# Mussol.net
KiCad netlist of a schematic drawn in EAGLE
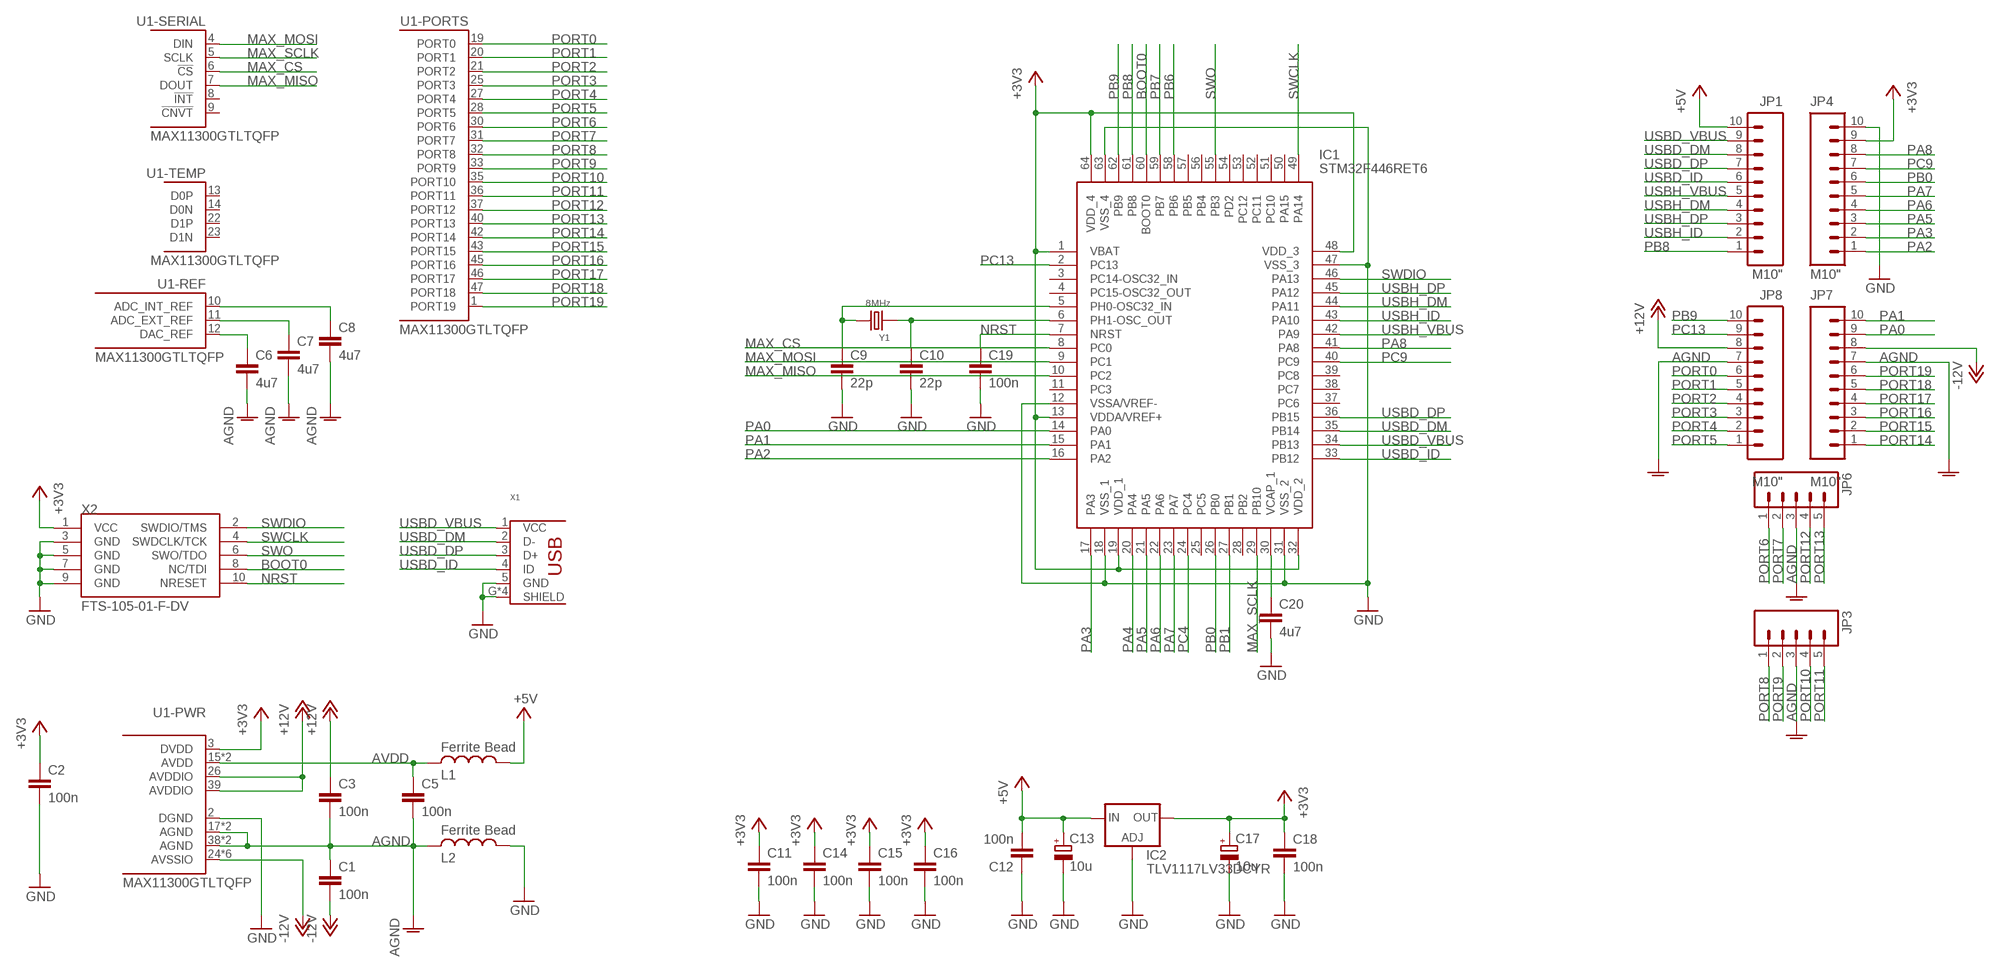
[diagram p0: schematic, sheet 1]

(export (version "E")
  (design (tool "Eeschema 10.0.6"))
  (components
    (comp (ref "C1")
      (value "100n")
      (footprint "eagle-import:C0402")
      (libsource (lib "eagle-import") (part "C-EUC0402"))
    )
    (comp (ref "C2")
      (value "100n")
      (footprint "eagle-import:C0402")
      (libsource (lib "eagle-import") (part "C-EUC0402"))
    )
    (comp (ref "C3")
      (value "100n")
      (footprint "eagle-import:C0402")
      (libsource (lib "eagle-import") (part "C-EUC0402"))
    )
    (comp (ref "C5")
      (value "100n")
      (footprint "eagle-import:C0402")
      (libsource (lib "eagle-import") (part "C-EUC0402"))
    )
    (comp (ref "C6")
      (value "4u7")
      (footprint "eagle-import:C0603")
      (libsource (lib "eagle-import") (part "C-EUC0603"))
    )
    (comp (ref "C7")
      (value "4u7")
      (footprint "eagle-import:C0603")
      (libsource (lib "eagle-import") (part "C-EUC0603"))
    )
    (comp (ref "C8")
      (value "4u7")
      (footprint "eagle-import:C0603")
      (libsource (lib "eagle-import") (part "C-EUC0603"))
    )
    (comp (ref "C9")
      (value "22p")
      (footprint "eagle-import:C0402")
      (libsource (lib "eagle-import") (part "C-EUC0402"))
    )
    (comp (ref "C10")
      (value "22p")
      (footprint "eagle-import:C0402")
      (libsource (lib "eagle-import") (part "C-EUC0402"))
    )
    (comp (ref "C11")
      (value "100n")
      (footprint "eagle-import:C0402")
      (libsource (lib "eagle-import") (part "C-EUC0402"))
    )
    (comp (ref "C12")
      (value "100n")
      (footprint "eagle-import:C0402")
      (libsource (lib "eagle-import") (part "C-EUC0402"))
    )
    (comp (ref "C13")
      (value "10u")
      (footprint "eagle-import:UD-4X5,8_NICHICON")
      (libsource (lib "eagle-import") (part "CPOL-EUUD-4X5,8"))
    )
    (comp (ref "C14")
      (value "100n")
      (footprint "eagle-import:C0402")
      (libsource (lib "eagle-import") (part "C-EUC0402"))
    )
    (comp (ref "C15")
      (value "100n")
      (footprint "eagle-import:C0402")
      (libsource (lib "eagle-import") (part "C-EUC0402"))
    )
    (comp (ref "C16")
      (value "100n")
      (footprint "eagle-import:C0402")
      (libsource (lib "eagle-import") (part "C-EUC0402"))
    )
    (comp (ref "C17")
      (value "10u")
      (footprint "eagle-import:UD-4X5,8_NICHICON")
      (libsource (lib "eagle-import") (part "CPOL-EUUD-4X5,8"))
    )
    (comp (ref "C18")
      (value "100n")
      (footprint "eagle-import:C0402")
      (libsource (lib "eagle-import") (part "C-EUC0402"))
    )
    (comp (ref "C19")
      (value "100n")
      (footprint "eagle-import:C0402")
      (libsource (lib "eagle-import") (part "C-EUC0402"))
    )
    (comp (ref "C20")
      (value "4u7")
      (footprint "eagle-import:C0603")
      (libsource (lib "eagle-import") (part "C-EUC0603"))
    )
    (comp (ref "IC1")
      (value "STM32F446RET6")
      (footprint "eagle-import:QFP50P1200X1200X160-64N")
      (fields
        (field (name "MOUSER_PART_NUMBER") "511-STM32F446RET6")
        (field (name "RS_PART_NUMBER") "1106621P")
      )
      (libsource (lib "eagle-import") (part "STM32F446RET6"))
    )
    (comp (ref "IC2")
      (value "TLV1117LV33DCYR")
      (footprint "eagle-import:SOT223")
      (libsource (lib "eagle-import") (part "LD117A?S33TR"))
    )
    (comp (ref "JP1")
      (value "M10\"")
      (footprint "eagle-import:1X10")
      (libsource (lib "eagle-import") (part "M10{dblquote}"))
    )
    (comp (ref "JP3")
      (value "M05PTH")
      (footprint "eagle-import:1X05")
      (libsource (lib "eagle-import") (part "M05PTH"))
    )
    (comp (ref "JP4")
      (value "M10\"")
      (footprint "eagle-import:1X10")
      (libsource (lib "eagle-import") (part "M10{dblquote}"))
    )
    (comp (ref "JP6")
      (value "M05PTH")
      (footprint "eagle-import:1X05")
      (libsource (lib "eagle-import") (part "M05PTH"))
    )
    (comp (ref "JP7")
      (value "M10\"")
      (footprint "eagle-import:1X10")
      (libsource (lib "eagle-import") (part "M10{dblquote}"))
    )
    (comp (ref "JP8")
      (value "M10\"")
      (footprint "eagle-import:1X10")
      (libsource (lib "eagle-import") (part "M10{dblquote}"))
    )
    (comp (ref "L1")
      (value "Ferrite Bead")
      (footprint "eagle-import:0603")
      (libsource (lib "eagle-import") (part "INDUCTOR"))
    )
    (comp (ref "L2")
      (value "Ferrite Bead")
      (footprint "eagle-import:0603")
      (libsource (lib "eagle-import") (part "INDUCTOR"))
    )
    (comp (ref "U1")
      (value "MAX11300GTLTQFP")
      (footprint "eagle-import:TQFP48")
      (libsource (lib "eagle-import") (part "MAX11300GTLTQFP"))
    )
    (comp (ref "X1")
      (value "USB_HRS_ZX62-B-5PA(11)MICRO.B")
      (footprint "eagle-import:HRS_ZX62RD-AB-5P8")
      (libsource (lib "eagle-import") (part "USB_HRS_ZX62-B-5PA(11)MICRO.B"))
    )
    (comp (ref "X2")
      (value "FTS-105-01-F-DV")
      (footprint "eagle-import:2X5_1.27MM_SMD")
      (libsource (lib "eagle-import") (part "ARM_10SMD"))
    )
    (comp (ref "Y1")
      (value "8MHz")
      (footprint "eagle-import:X2-SMD-5.0X3.2X1.3MM")
      (fields (field (name "MPN") "5032/2P"))
      (libsource (lib "eagle-import") (part "SMD-CRYSTAL-8MHZ-20PF-20PPM(2P-5.0X3.2MM)"))
    )
  )
  (nets
    (net (code "1") (name "+3V3") (class "Default")
      (node (ref "C11") (pin "1") (pinfunction "1_1") (pintype "passive"))
      (node (ref "C14") (pin "1") (pinfunction "1_1") (pintype "passive"))
      (node (ref "C15") (pin "1") (pinfunction "1_1") (pintype "passive"))
      (node (ref "C16") (pin "1") (pinfunction "1_1") (pintype "passive"))
      (node (ref "C17") (pin "+") (pinfunction "+_+") (pintype "passive"))
      (node (ref "C18") (pin "1") (pinfunction "1_1") (pintype "passive"))
      (node (ref "C2") (pin "1") (pinfunction "1_1") (pintype "passive"))
      (node (ref "IC1") (pin "1") (pinfunction "VBAT_1") (pintype "bidirectional"))
      (node (ref "IC1") (pin "13") (pinfunction "VDDA/VREF+_13") (pintype "bidirectional"))
      (node (ref "IC1") (pin "19") (pinfunction "VDD_1_19") (pintype "bidirectional"))
      (node (ref "IC1") (pin "32") (pinfunction "VDD_2_32") (pintype "bidirectional"))
      (node (ref "IC1") (pin "48") (pinfunction "VDD_3_48") (pintype "bidirectional"))
      (node (ref "IC1") (pin "64") (pinfunction "VDD_4_64") (pintype "bidirectional"))
      (node (ref "IC2") (pin "4") (pinfunction "OUT_4") (pintype "passive"))
      (node (ref "JP4") (pin "9") (pinfunction "9_9") (pintype "passive"))
      (node (ref "U1") (pin "3") (pinfunction "DVDD_3") (pintype "bidirectional"))
      (node (ref "X2") (pin "1") (pinfunction "VCC_1") (pintype "bidirectional"))
    )
    (net (code "2") (name "+5V") (class "Default")
      (node (ref "C12") (pin "2") (pinfunction "2_2") (pintype "passive"))
      (node (ref "C13") (pin "+") (pinfunction "+_+") (pintype "passive"))
      (node (ref "IC2") (pin "3") (pinfunction "IN_3") (pintype "input"))
      (node (ref "JP1") (pin "10") (pinfunction "10_10") (pintype "passive"))
      (node (ref "L1") (pin "1") (pinfunction "1_1") (pintype "passive"))
    )
    (net (code "3") (name "+12V") (class "Default")
      (node (ref "C3") (pin "1") (pinfunction "1_1") (pintype "passive"))
      (node (ref "JP8") (pin "8") (pinfunction "8_8") (pintype "passive"))
      (node (ref "U1") (pin "26") (pinfunction "AVDDIO_26") (pintype "bidirectional"))
      (node (ref "U1") (pin "39") (pinfunction "AVDDIO_39") (pintype "bidirectional"))
    )
    (net (code "4") (name "-12V") (class "Default")
      (node (ref "C1") (pin "2") (pinfunction "2_2") (pintype "passive"))
      (node (ref "JP7") (pin "8") (pinfunction "8_8") (pintype "passive"))
      (node (ref "U1") (pin "24") (pinfunction "AVSSIO_24") (pintype "bidirectional"))
      (node (ref "U1") (pin "29") (pinfunction "AVSSIO_29") (pintype "bidirectional"))
      (node (ref "U1") (pin "34") (pinfunction "AVSSIO_34") (pintype "bidirectional"))
      (node (ref "U1") (pin "41") (pinfunction "AVSSIO_41") (pintype "bidirectional"))
      (node (ref "U1") (pin "44") (pinfunction "AVSSIO_44") (pintype "bidirectional"))
      (node (ref "U1") (pin "48") (pinfunction "AVSSIO_48") (pintype "bidirectional"))
    )
    (net (code "5") (name "/AVDD") (class "Default")
      (node (ref "C5") (pin "1") (pinfunction "1_1") (pintype "passive"))
      (node (ref "L1") (pin "2") (pinfunction "2_2") (pintype "passive"))
      (node (ref "U1") (pin "15") (pinfunction "AVDD_15") (pintype "bidirectional"))
      (node (ref "U1") (pin "16") (pinfunction "AVDD_16") (pintype "bidirectional"))
    )
    (net (code "6") (name "/BOOT0") (class "Default")
      (node (ref "IC1") (pin "60") (pinfunction "BOOT0_60") (pintype "bidirectional"))
      (node (ref "X2") (pin "8") (pinfunction "NC/TDI_8") (pintype "bidirectional"))
    )
    (net (code "7") (name "/MAX_CS") (class "Default")
      (node (ref "IC1") (pin "8") (pinfunction "PC0_8") (pintype "bidirectional"))
      (node (ref "U1") (pin "6") (pinfunction "~{CS}_6") (pintype "bidirectional"))
    )
    (net (code "8") (name "/MAX_MISO") (class "Default")
      (node (ref "IC1") (pin "10") (pinfunction "PC2_10") (pintype "bidirectional"))
      (node (ref "U1") (pin "7") (pinfunction "DOUT_7") (pintype "bidirectional"))
    )
    (net (code "9") (name "/MAX_MOSI") (class "Default")
      (node (ref "IC1") (pin "9") (pinfunction "PC1_9") (pintype "bidirectional"))
      (node (ref "U1") (pin "4") (pinfunction "DIN_4") (pintype "bidirectional"))
    )
    (net (code "10") (name "/MAX_SCLK") (class "Default")
      (node (ref "IC1") (pin "29") (pinfunction "PB10_29") (pintype "bidirectional"))
      (node (ref "U1") (pin "5") (pinfunction "SCLK_5") (pintype "bidirectional"))
    )
    (net (code "11") (name "/NRST") (class "Default")
      (node (ref "C19") (pin "1") (pinfunction "1_1") (pintype "passive"))
      (node (ref "IC1") (pin "7") (pinfunction "NRST_7") (pintype "bidirectional"))
      (node (ref "X2") (pin "10") (pinfunction "NRESET_10") (pintype "bidirectional"))
    )
    (net (code "12") (name "/PA0") (class "Default")
      (node (ref "IC1") (pin "14") (pinfunction "PA0_14") (pintype "bidirectional"))
      (node (ref "JP7") (pin "9") (pinfunction "9_9") (pintype "passive"))
    )
    (net (code "13") (name "/PA1") (class "Default")
      (node (ref "IC1") (pin "15") (pinfunction "PA1_15") (pintype "bidirectional"))
      (node (ref "JP7") (pin "10") (pinfunction "10_10") (pintype "passive"))
    )
    (net (code "14") (name "/PA2") (class "Default")
      (node (ref "IC1") (pin "16") (pinfunction "PA2_16") (pintype "bidirectional"))
      (node (ref "JP4") (pin "1") (pinfunction "1_1") (pintype "passive"))
    )
    (net (code "15") (name "/PA3") (class "Default")
      (node (ref "IC1") (pin "17") (pinfunction "PA3_17") (pintype "bidirectional"))
      (node (ref "JP4") (pin "2") (pinfunction "2_2") (pintype "passive"))
    )
    (net (code "16") (name "/PA4") (class "Default")
      (node (ref "IC1") (pin "20") (pinfunction "PA4_20") (pintype "bidirectional"))
    )
    (net (code "17") (name "/PA5") (class "Default")
      (node (ref "IC1") (pin "21") (pinfunction "PA5_21") (pintype "bidirectional"))
      (node (ref "JP4") (pin "3") (pinfunction "3_3") (pintype "passive"))
    )
    (net (code "18") (name "/PA6") (class "Default")
      (node (ref "IC1") (pin "22") (pinfunction "PA6_22") (pintype "bidirectional"))
      (node (ref "JP4") (pin "4") (pinfunction "4_4") (pintype "passive"))
    )
    (net (code "19") (name "/PA7") (class "Default")
      (node (ref "IC1") (pin "23") (pinfunction "PA7_23") (pintype "bidirectional"))
      (node (ref "JP4") (pin "5") (pinfunction "5_5") (pintype "passive"))
    )
    (net (code "20") (name "/PA8") (class "Default")
      (node (ref "IC1") (pin "41") (pinfunction "PA8_41") (pintype "bidirectional"))
      (node (ref "JP4") (pin "8") (pinfunction "8_8") (pintype "passive"))
    )
    (net (code "21") (name "/PB0") (class "Default")
      (node (ref "IC1") (pin "26") (pinfunction "PB0_26") (pintype "bidirectional"))
      (node (ref "JP4") (pin "6") (pinfunction "6_6") (pintype "passive"))
    )
    (net (code "22") (name "/PB1") (class "Default")
      (node (ref "IC1") (pin "27") (pinfunction "PB1_27") (pintype "bidirectional"))
    )
    (net (code "23") (name "/PB6") (class "Default")
      (node (ref "IC1") (pin "58") (pinfunction "PB6_58") (pintype "bidirectional"))
    )
    (net (code "24") (name "/PB7") (class "Default")
      (node (ref "IC1") (pin "59") (pinfunction "PB7_59") (pintype "bidirectional"))
    )
    (net (code "25") (name "/PB8") (class "Default")
      (node (ref "IC1") (pin "61") (pinfunction "PB8_61") (pintype "bidirectional"))
      (node (ref "JP1") (pin "1") (pinfunction "1_1") (pintype "passive"))
    )
    (net (code "26") (name "/PB9") (class "Default")
      (node (ref "IC1") (pin "62") (pinfunction "PB9_62") (pintype "bidirectional"))
      (node (ref "JP8") (pin "10") (pinfunction "10_10") (pintype "passive"))
    )
    (net (code "27") (name "/PC4") (class "Default")
      (node (ref "IC1") (pin "24") (pinfunction "PC4_24") (pintype "bidirectional"))
    )
    (net (code "28") (name "/PC9") (class "Default")
      (node (ref "IC1") (pin "40") (pinfunction "PC9_40") (pintype "bidirectional"))
      (node (ref "JP4") (pin "7") (pinfunction "7_7") (pintype "passive"))
    )
    (net (code "29") (name "/PC13") (class "Default")
      (node (ref "IC1") (pin "2") (pinfunction "PC13_2") (pintype "bidirectional"))
      (node (ref "JP8") (pin "9") (pinfunction "9_9") (pintype "passive"))
    )
    (net (code "30") (name "/PORT0") (class "Default")
      (node (ref "JP8") (pin "6") (pinfunction "6_6") (pintype "passive"))
      (node (ref "U1") (pin "19") (pinfunction "PORT0_19") (pintype "bidirectional"))
    )
    (net (code "31") (name "/PORT1") (class "Default")
      (node (ref "JP8") (pin "5") (pinfunction "5_5") (pintype "passive"))
      (node (ref "U1") (pin "20") (pinfunction "PORT1_20") (pintype "bidirectional"))
    )
    (net (code "32") (name "/PORT2") (class "Default")
      (node (ref "JP8") (pin "4") (pinfunction "4_4") (pintype "passive"))
      (node (ref "U1") (pin "21") (pinfunction "PORT2_21") (pintype "bidirectional"))
    )
    (net (code "33") (name "/PORT3") (class "Default")
      (node (ref "JP8") (pin "3") (pinfunction "3_3") (pintype "passive"))
      (node (ref "U1") (pin "25") (pinfunction "PORT3_25") (pintype "bidirectional"))
    )
    (net (code "34") (name "/PORT4") (class "Default")
      (node (ref "JP8") (pin "2") (pinfunction "2_2") (pintype "passive"))
      (node (ref "U1") (pin "27") (pinfunction "PORT4_27") (pintype "bidirectional"))
    )
    (net (code "35") (name "/PORT5") (class "Default")
      (node (ref "JP8") (pin "1") (pinfunction "1_1") (pintype "passive"))
      (node (ref "U1") (pin "28") (pinfunction "PORT5_28") (pintype "bidirectional"))
    )
    (net (code "36") (name "/PORT6") (class "Default")
      (node (ref "JP6") (pin "1") (pinfunction "1_1") (pintype "passive"))
      (node (ref "U1") (pin "30") (pinfunction "PORT6_30") (pintype "bidirectional"))
    )
    (net (code "37") (name "/PORT7") (class "Default")
      (node (ref "JP6") (pin "2") (pinfunction "2_2") (pintype "passive"))
      (node (ref "U1") (pin "31") (pinfunction "PORT7_31") (pintype "bidirectional"))
    )
    (net (code "38") (name "/PORT8") (class "Default")
      (node (ref "JP3") (pin "1") (pinfunction "1_1") (pintype "passive"))
      (node (ref "U1") (pin "32") (pinfunction "PORT8_32") (pintype "bidirectional"))
    )
    (net (code "39") (name "/PORT9") (class "Default")
      (node (ref "JP3") (pin "2") (pinfunction "2_2") (pintype "passive"))
      (node (ref "U1") (pin "33") (pinfunction "PORT9_33") (pintype "bidirectional"))
    )
    (net (code "40") (name "/PORT10") (class "Default")
      (node (ref "JP3") (pin "4") (pinfunction "4_4") (pintype "passive"))
      (node (ref "U1") (pin "35") (pinfunction "PORT10_35") (pintype "bidirectional"))
    )
    (net (code "41") (name "/PORT11") (class "Default")
      (node (ref "JP3") (pin "5") (pinfunction "5_5") (pintype "passive"))
      (node (ref "U1") (pin "36") (pinfunction "PORT11_36") (pintype "bidirectional"))
    )
    (net (code "42") (name "/PORT12") (class "Default")
      (node (ref "JP6") (pin "4") (pinfunction "4_4") (pintype "passive"))
      (node (ref "U1") (pin "37") (pinfunction "PORT12_37") (pintype "bidirectional"))
    )
    (net (code "43") (name "/PORT13") (class "Default")
      (node (ref "JP6") (pin "5") (pinfunction "5_5") (pintype "passive"))
      (node (ref "U1") (pin "40") (pinfunction "PORT13_40") (pintype "bidirectional"))
    )
    (net (code "44") (name "/PORT14") (class "Default")
      (node (ref "JP7") (pin "1") (pinfunction "1_1") (pintype "passive"))
      (node (ref "U1") (pin "42") (pinfunction "PORT14_42") (pintype "bidirectional"))
    )
    (net (code "45") (name "/PORT15") (class "Default")
      (node (ref "JP7") (pin "2") (pinfunction "2_2") (pintype "passive"))
      (node (ref "U1") (pin "43") (pinfunction "PORT15_43") (pintype "bidirectional"))
    )
    (net (code "46") (name "/PORT16") (class "Default")
      (node (ref "JP7") (pin "3") (pinfunction "3_3") (pintype "passive"))
      (node (ref "U1") (pin "45") (pinfunction "PORT16_45") (pintype "bidirectional"))
    )
    (net (code "47") (name "/PORT17") (class "Default")
      (node (ref "JP7") (pin "4") (pinfunction "4_4") (pintype "passive"))
      (node (ref "U1") (pin "46") (pinfunction "PORT17_46") (pintype "bidirectional"))
    )
    (net (code "48") (name "/PORT18") (class "Default")
      (node (ref "JP7") (pin "5") (pinfunction "5_5") (pintype "passive"))
      (node (ref "U1") (pin "47") (pinfunction "PORT18_47") (pintype "bidirectional"))
    )
    (net (code "49") (name "/PORT19") (class "Default")
      (node (ref "JP7") (pin "6") (pinfunction "6_6") (pintype "passive"))
      (node (ref "U1") (pin "1") (pinfunction "PORT19_1") (pintype "bidirectional"))
    )
    (net (code "50") (name "/SWCLK") (class "Default")
      (node (ref "IC1") (pin "49") (pinfunction "PA14_49") (pintype "bidirectional"))
      (node (ref "X2") (pin "4") (pinfunction "SWDCLK/TCK_4") (pintype "bidirectional"))
    )
    (net (code "51") (name "/SWDIO") (class "Default")
      (node (ref "IC1") (pin "46") (pinfunction "PA13_46") (pintype "bidirectional"))
      (node (ref "X2") (pin "2") (pinfunction "SWDIO/TMS_2") (pintype "bidirectional"))
    )
    (net (code "52") (name "/SWO") (class "Default")
      (node (ref "IC1") (pin "55") (pinfunction "PB3_55") (pintype "bidirectional"))
      (node (ref "X2") (pin "6") (pinfunction "SWO/TDO_6") (pintype "bidirectional"))
    )
    (net (code "53") (name "/USBD_DM") (class "Default")
      (node (ref "IC1") (pin "35") (pinfunction "PB14_35") (pintype "bidirectional"))
      (node (ref "JP1") (pin "8") (pinfunction "8_8") (pintype "passive"))
      (node (ref "X1") (pin "2") (pinfunction "D-_2") (pintype "bidirectional"))
    )
    (net (code "54") (name "/USBD_DP") (class "Default")
      (node (ref "IC1") (pin "36") (pinfunction "PB15_36") (pintype "bidirectional"))
      (node (ref "JP1") (pin "7") (pinfunction "7_7") (pintype "passive"))
      (node (ref "X1") (pin "3") (pinfunction "D+_3") (pintype "bidirectional"))
    )
    (net (code "55") (name "/USBD_ID") (class "Default")
      (node (ref "IC1") (pin "33") (pinfunction "PB12_33") (pintype "bidirectional"))
      (node (ref "JP1") (pin "6") (pinfunction "6_6") (pintype "passive"))
      (node (ref "X1") (pin "4") (pinfunction "ID_4") (pintype "bidirectional"))
    )
    (net (code "56") (name "/USBD_VBUS") (class "Default")
      (node (ref "IC1") (pin "34") (pinfunction "PB13_34") (pintype "bidirectional"))
      (node (ref "JP1") (pin "9") (pinfunction "9_9") (pintype "passive"))
      (node (ref "X1") (pin "1") (pinfunction "VCC_1") (pintype "bidirectional"))
    )
    (net (code "57") (name "/USBH_DM") (class "Default")
      (node (ref "IC1") (pin "44") (pinfunction "PA11_44") (pintype "bidirectional"))
      (node (ref "JP1") (pin "4") (pinfunction "4_4") (pintype "passive"))
    )
    (net (code "58") (name "/USBH_DP") (class "Default")
      (node (ref "IC1") (pin "45") (pinfunction "PA12_45") (pintype "bidirectional"))
      (node (ref "JP1") (pin "3") (pinfunction "3_3") (pintype "passive"))
    )
    (net (code "59") (name "/USBH_ID") (class "Default")
      (node (ref "IC1") (pin "43") (pinfunction "PA10_43") (pintype "bidirectional"))
      (node (ref "JP1") (pin "2") (pinfunction "2_2") (pintype "passive"))
    )
    (net (code "60") (name "/USBH_VBUS") (class "Default")
      (node (ref "IC1") (pin "42") (pinfunction "PA9_42") (pintype "bidirectional"))
      (node (ref "JP1") (pin "5") (pinfunction "5_5") (pintype "passive"))
    )
    (net (code "61") (name "AGND") (class "Default")
      (node (ref "C1") (pin "1") (pinfunction "1_1") (pintype "passive"))
      (node (ref "C3") (pin "2") (pinfunction "2_2") (pintype "passive"))
      (node (ref "C5") (pin "2") (pinfunction "2_2") (pintype "passive"))
      (node (ref "C6") (pin "2") (pinfunction "2_2") (pintype "passive"))
      (node (ref "C7") (pin "2") (pinfunction "2_2") (pintype "passive"))
      (node (ref "C8") (pin "2") (pinfunction "2_2") (pintype "passive"))
      (node (ref "JP3") (pin "3") (pinfunction "3_3") (pintype "passive"))
      (node (ref "JP6") (pin "3") (pinfunction "3_3") (pintype "passive"))
      (node (ref "JP7") (pin "7") (pinfunction "7_7") (pintype "passive"))
      (node (ref "JP8") (pin "7") (pinfunction "7_7") (pintype "passive"))
      (node (ref "L2") (pin "2") (pinfunction "2_2") (pintype "passive"))
      (node (ref "U1") (pin "17") (pinfunction "AGND_17") (pintype "bidirectional"))
      (node (ref "U1") (pin "18") (pinfunction "AGND_18") (pintype "bidirectional"))
      (node (ref "U1") (pin "38") (pinfunction "AGND_38") (pintype "bidirectional"))
      (node (ref "U1") (pin "EP") (pinfunction "AGND_EP") (pintype "bidirectional"))
    )
    (net (code "62") (name "GND") (class "Default")
      (node (ref "C10") (pin "2") (pinfunction "2_2") (pintype "passive"))
      (node (ref "C11") (pin "2") (pinfunction "2_2") (pintype "passive"))
      (node (ref "C12") (pin "1") (pinfunction "1_1") (pintype "passive"))
      (node (ref "C13") (pin "-") (pinfunction "-_-") (pintype "passive"))
      (node (ref "C14") (pin "2") (pinfunction "2_2") (pintype "passive"))
      (node (ref "C15") (pin "2") (pinfunction "2_2") (pintype "passive"))
      (node (ref "C16") (pin "2") (pinfunction "2_2") (pintype "passive"))
      (node (ref "C17") (pin "-") (pinfunction "-_-") (pintype "passive"))
      (node (ref "C18") (pin "2") (pinfunction "2_2") (pintype "passive"))
      (node (ref "C19") (pin "2") (pinfunction "2_2") (pintype "passive"))
      (node (ref "C2") (pin "2") (pinfunction "2_2") (pintype "passive"))
      (node (ref "C20") (pin "2") (pinfunction "2_2") (pintype "passive"))
      (node (ref "C9") (pin "2") (pinfunction "2_2") (pintype "passive"))
      (node (ref "IC1") (pin "12") (pinfunction "VSSA/VREF-_12") (pintype "bidirectional"))
      (node (ref "IC1") (pin "18") (pinfunction "VSS_1_18") (pintype "bidirectional"))
      (node (ref "IC1") (pin "31") (pinfunction "VSS_2_31") (pintype "bidirectional"))
      (node (ref "IC1") (pin "47") (pinfunction "VSS_3_47") (pintype "bidirectional"))
      (node (ref "IC1") (pin "63") (pinfunction "VSS_4_63") (pintype "bidirectional"))
      (node (ref "IC2") (pin "1") (pinfunction "ADJ_1") (pintype "input"))
      (node (ref "JP4") (pin "10") (pinfunction "10_10") (pintype "passive"))
      (node (ref "L2") (pin "1") (pinfunction "1_1") (pintype "passive"))
      (node (ref "U1") (pin "2") (pinfunction "DGND_2") (pintype "bidirectional"))
      (node (ref "X1") (pin "5") (pinfunction "GND_5") (pintype "bidirectional"))
      (node (ref "X1") (pin "G") (pinfunction "SHIELD_G") (pintype "bidirectional"))
      (node (ref "X1") (pin "G2") (pinfunction "SHIELD_G2") (pintype "bidirectional"))
      (node (ref "X1") (pin "G3") (pinfunction "SHIELD_G3") (pintype "bidirectional"))
      (node (ref "X1") (pin "G4") (pinfunction "SHIELD_G4") (pintype "bidirectional"))
      (node (ref "X2") (pin "3") (pinfunction "GND_3") (pintype "bidirectional"))
      (node (ref "X2") (pin "5") (pinfunction "GND_5") (pintype "bidirectional"))
      (node (ref "X2") (pin "7") (pinfunction "GND_7") (pintype "bidirectional"))
      (node (ref "X2") (pin "9") (pinfunction "GND_9") (pintype "bidirectional"))
    )
    (net (code "63") (name "Net-(IC1-PH0-OSC32_IN)") (class "Default")
      (node (ref "C9") (pin "1") (pinfunction "1_1") (pintype "passive"))
      (node (ref "IC1") (pin "5") (pinfunction "PH0-OSC32_IN_5") (pintype "bidirectional"))
      (node (ref "Y1") (pin "2") (pinfunction "2_2") (pintype "passive"))
    )
    (net (code "64") (name "Net-(IC1-PH1-OSC_OUT)") (class "Default")
      (node (ref "C10") (pin "1") (pinfunction "1_1") (pintype "passive"))
      (node (ref "IC1") (pin "6") (pinfunction "PH1-OSC_OUT_6") (pintype "bidirectional"))
      (node (ref "Y1") (pin "1") (pinfunction "1_1") (pintype "passive"))
    )
    (net (code "65") (name "Net-(IC1-VCAP_1)") (class "Default")
      (node (ref "C20") (pin "1") (pinfunction "1_1") (pintype "passive"))
      (node (ref "IC1") (pin "30") (pinfunction "VCAP_1_30") (pintype "bidirectional"))
    )
    (net (code "66") (name "Net-(U1C-ADC_EXT_REF)") (class "Default")
      (node (ref "C7") (pin "1") (pinfunction "1_1") (pintype "passive"))
      (node (ref "U1") (pin "11") (pinfunction "ADC_EXT_REF_11") (pintype "bidirectional"))
    )
    (net (code "67") (name "Net-(U1C-ADC_INT_REF)") (class "Default")
      (node (ref "C8") (pin "1") (pinfunction "1_1") (pintype "passive"))
      (node (ref "U1") (pin "10") (pinfunction "ADC_INT_REF_10") (pintype "bidirectional"))
    )
    (net (code "68") (name "Net-(U1C-DAC_REF)") (class "Default")
      (node (ref "C6") (pin "1") (pinfunction "1_1") (pintype "passive"))
      (node (ref "U1") (pin "12") (pinfunction "DAC_REF_12") (pintype "bidirectional"))
    )
    (net (code "69") (name "unconnected-(IC1-PA15-Pad50)") (class "Default")
      (node (ref "IC1") (pin "50") (pinfunction "PA15_50") (pintype "bidirectional"))
    )
    (net (code "70") (name "unconnected-(IC1-PB2-Pad28)") (class "Default")
      (node (ref "IC1") (pin "28") (pinfunction "PB2_28") (pintype "bidirectional"))
    )
    (net (code "71") (name "unconnected-(IC1-PB4-Pad56)") (class "Default")
      (node (ref "IC1") (pin "56") (pinfunction "PB4_56") (pintype "bidirectional"))
    )
    (net (code "72") (name "unconnected-(IC1-PB5-Pad57)") (class "Default")
      (node (ref "IC1") (pin "57") (pinfunction "PB5_57") (pintype "bidirectional"))
    )
    (net (code "73") (name "unconnected-(IC1-PC3-Pad11)") (class "Default")
      (node (ref "IC1") (pin "11") (pinfunction "PC3_11") (pintype "bidirectional"))
    )
    (net (code "74") (name "unconnected-(IC1-PC5-Pad25)") (class "Default")
      (node (ref "IC1") (pin "25") (pinfunction "PC5_25") (pintype "bidirectional"))
    )
    (net (code "75") (name "unconnected-(IC1-PC6-Pad37)") (class "Default")
      (node (ref "IC1") (pin "37") (pinfunction "PC6_37") (pintype "bidirectional"))
    )
    (net (code "76") (name "unconnected-(IC1-PC7-Pad38)") (class "Default")
      (node (ref "IC1") (pin "38") (pinfunction "PC7_38") (pintype "bidirectional"))
    )
    (net (code "77") (name "unconnected-(IC1-PC8-Pad39)") (class "Default")
      (node (ref "IC1") (pin "39") (pinfunction "PC8_39") (pintype "bidirectional"))
    )
    (net (code "78") (name "unconnected-(IC1-PC10-Pad51)") (class "Default")
      (node (ref "IC1") (pin "51") (pinfunction "PC10_51") (pintype "bidirectional"))
    )
    (net (code "79") (name "unconnected-(IC1-PC11-Pad52)") (class "Default")
      (node (ref "IC1") (pin "52") (pinfunction "PC11_52") (pintype "bidirectional"))
    )
    (net (code "80") (name "unconnected-(IC1-PC12-Pad53)") (class "Default")
      (node (ref "IC1") (pin "53") (pinfunction "PC12_53") (pintype "bidirectional"))
    )
    (net (code "81") (name "unconnected-(IC1-PC14-OSC32_IN-Pad3)") (class "Default")
      (node (ref "IC1") (pin "3") (pinfunction "PC14-OSC32_IN_3") (pintype "bidirectional"))
    )
    (net (code "82") (name "unconnected-(IC1-PC15-OSC32_OUT-Pad4)") (class "Default")
      (node (ref "IC1") (pin "4") (pinfunction "PC15-OSC32_OUT_4") (pintype "bidirectional"))
    )
    (net (code "83") (name "unconnected-(IC1-PD2-Pad54)") (class "Default")
      (node (ref "IC1") (pin "54") (pinfunction "PD2_54") (pintype "bidirectional"))
    )
    (net (code "84") (name "unconnected-(U1D-~{CNVT}-Pad9)") (class "Default")
      (node (ref "U1") (pin "9") (pinfunction "~{CNVT}_9") (pintype "bidirectional"))
    )
    (net (code "85") (name "unconnected-(U1D-~{INT}-Pad8)") (class "Default")
      (node (ref "U1") (pin "8") (pinfunction "~{INT}_8") (pintype "bidirectional"))
    )
    (net (code "86") (name "unconnected-(U1E-D0N-Pad14)") (class "Default")
      (node (ref "U1") (pin "14") (pinfunction "D0N_14") (pintype "bidirectional"))
    )
    (net (code "87") (name "unconnected-(U1E-D0P-Pad13)") (class "Default")
      (node (ref "U1") (pin "13") (pinfunction "D0P_13") (pintype "bidirectional"))
    )
    (net (code "88") (name "unconnected-(U1E-D1N-Pad23)") (class "Default")
      (node (ref "U1") (pin "23") (pinfunction "D1N_23") (pintype "bidirectional"))
    )
    (net (code "89") (name "unconnected-(U1E-D1P-Pad22)") (class "Default")
      (node (ref "U1") (pin "22") (pinfunction "D1P_22") (pintype "bidirectional"))
    )
  )
)
